# TC364_MainBoard_Power_V1_0.net
KiCad netlist of a schematic drawn in Altium Designer
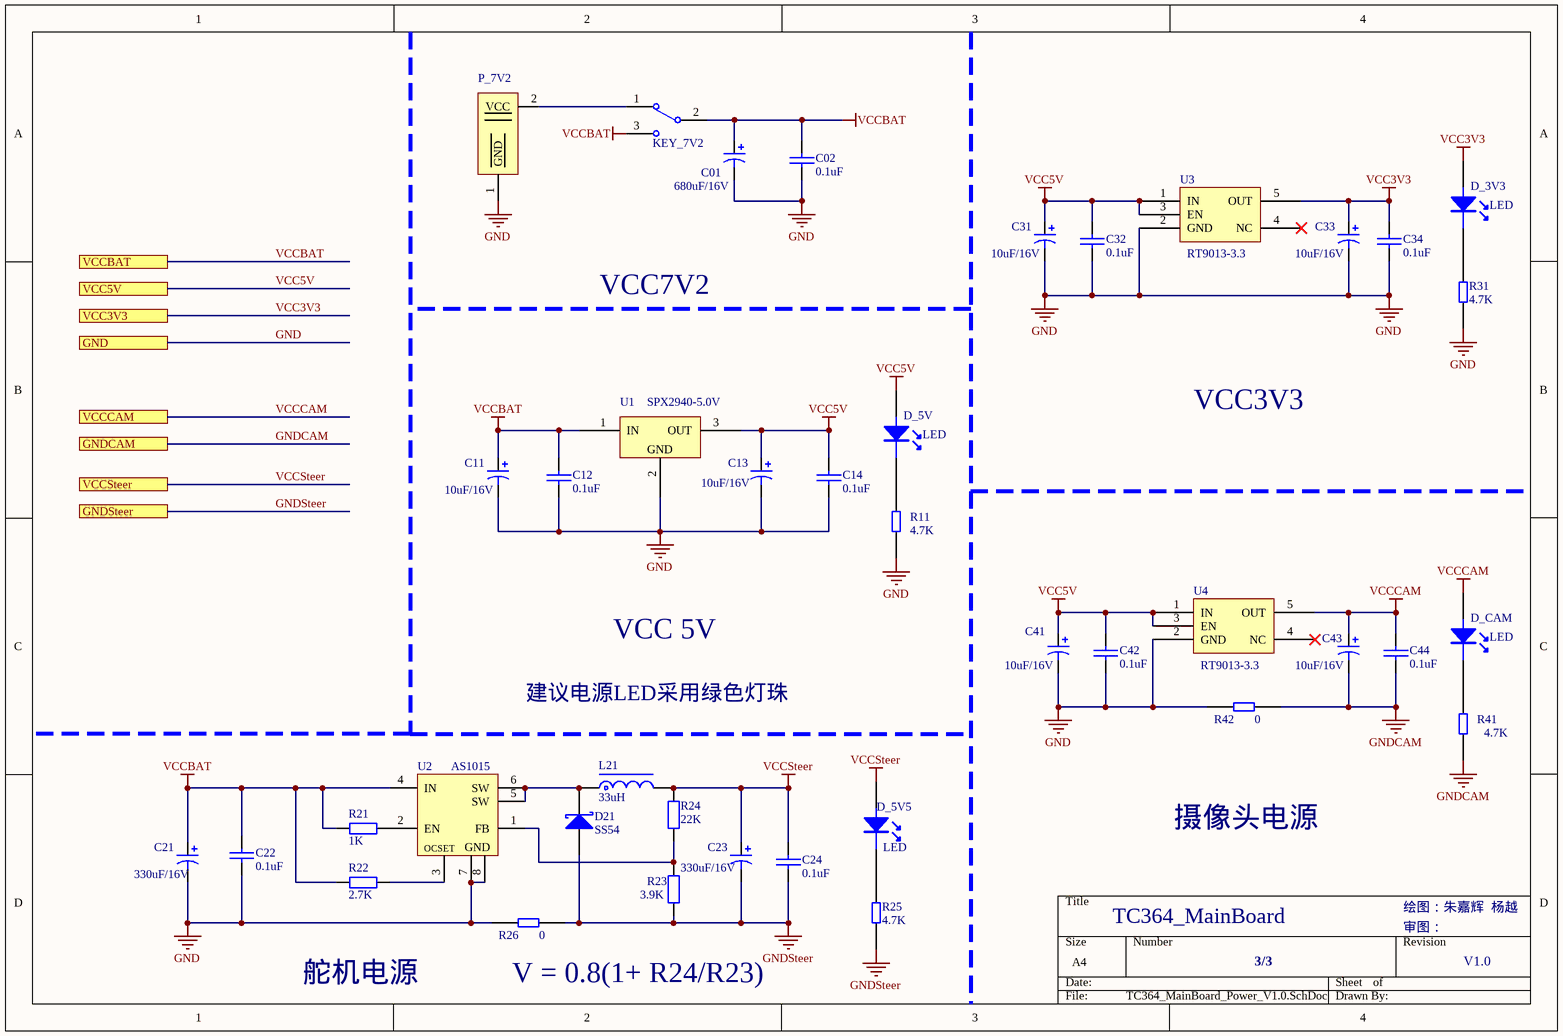
[diagram p0: TC364_MainBoard_Power_V1.0.SchDoc]

(export (version "E")
  (design (tool "Eeschema 10.0.6"))
  (components
    (comp (ref "C01")
      (value "680uF/16V")
      (footprint "CAP 3.5*8*11.5 - GD")
      (description "Polarized Capacitor (Radial)")
      (fields (field (name "PUBLISHER") "Altium Limited"))
      (libsource (lib "Miscellaneous Devices") (part "Cap Pol1"))
    )
    (comp (ref "C02")
      (value "0.1uF")
      (footprint "0805_C")
      (description "Capacitor")
      (libsource (lib "Protel99Lib_SCH") (part "CAP"))
    )
    (comp (ref "C11")
      (value "10uF/16V")
      (footprint "CASE-A_3216")
      (description "Polarized Capacitor (Radial)")
      (fields (field (name "PUBLISHER") "Altium Limited"))
      (libsource (lib "Miscellaneous Devices") (part "Cap Pol1"))
    )
    (comp (ref "C12")
      (value "0.1uF")
      (footprint "0805_C")
      (description "Capacitor")
      (libsource (lib "Protel99Lib_SCH") (part "CAP"))
    )
    (comp (ref "C13")
      (value "10uF/16V")
      (footprint "CASE-A_3216")
      (description "Polarized Capacitor (Radial)")
      (fields (field (name "PUBLISHER") "Altium Limited"))
      (libsource (lib "Miscellaneous Devices") (part "Cap Pol1"))
    )
    (comp (ref "C14")
      (value "0.1uF")
      (footprint "0805_C")
      (description "Capacitor")
      (libsource (lib "Protel99Lib_SCH") (part "CAP"))
    )
    (comp (ref "C21")
      (value "330uF/16V")
      (footprint "CAP 2.5*6.3*11.2 - BK")
      (description "Polarized Capacitor (Radial)")
      (fields (field (name "PUBLISHER") "Altium Limited"))
      (libsource (lib "Miscellaneous Devices") (part "Cap Pol1"))
    )
    (comp (ref "C22")
      (value "0.1uF")
      (footprint "0805_C")
      (description "Capacitor")
      (libsource (lib "Protel99Lib_SCH") (part "CAP"))
    )
    (comp (ref "C23")
      (value "330uF/16V")
      (footprint "CAP 2.5*6.3*11.2 - BK")
      (description "Polarized Capacitor (Radial)")
      (fields (field (name "PUBLISHER") "Altium Limited"))
      (libsource (lib "Miscellaneous Devices") (part "Cap Pol1"))
    )
    (comp (ref "C24")
      (value "0.1uF")
      (footprint "0805_C")
      (description "Capacitor")
      (libsource (lib "Protel99Lib_SCH") (part "CAP"))
    )
    (comp (ref "C31")
      (value "10uF/16V")
      (footprint "CASE-A_3216")
      (description "Polarized Capacitor (Radial)")
      (fields (field (name "PUBLISHER") "Altium Limited"))
      (libsource (lib "Miscellaneous Devices") (part "Cap Pol1"))
    )
    (comp (ref "C32")
      (value "0.1uF")
      (footprint "0805_C")
      (description "Capacitor")
      (libsource (lib "Protel99Lib_SCH") (part "CAP"))
    )
    (comp (ref "C33")
      (value "10uF/16V")
      (footprint "CASE-A_3216")
      (description "Polarized Capacitor (Radial)")
      (fields (field (name "PUBLISHER") "Altium Limited"))
      (libsource (lib "Miscellaneous Devices") (part "Cap Pol1"))
    )
    (comp (ref "C34")
      (value "0.1uF")
      (footprint "0805_C")
      (description "Capacitor")
      (libsource (lib "Protel99Lib_SCH") (part "CAP"))
    )
    (comp (ref "C41")
      (value "10uF/16V")
      (footprint "CASE-A_3216")
      (description "Polarized Capacitor (Radial)")
      (fields (field (name "PUBLISHER") "Altium Limited"))
      (libsource (lib "Miscellaneous Devices") (part "Cap Pol1"))
    )
    (comp (ref "C42")
      (value "0.1uF")
      (footprint "0805_C")
      (description "Capacitor")
      (libsource (lib "Protel99Lib_SCH") (part "CAP"))
    )
    (comp (ref "C43")
      (value "10uF/16V")
      (footprint "CASE-A_3216")
      (description "Polarized Capacitor (Radial)")
      (fields (field (name "PUBLISHER") "Altium Limited"))
      (libsource (lib "Miscellaneous Devices") (part "Cap Pol1"))
    )
    (comp (ref "C44")
      (value "0.1uF")
      (footprint "0805_C")
      (description "Capacitor")
      (libsource (lib "Protel99Lib_SCH") (part "CAP"))
    )
    (comp (ref "D21")
      (value "SS54")
      (footprint "SMA")
      (description "肖特基二极管")
      (libsource (lib "0.2 -  二极管-整流桥") (part "SS34"))
    )
    (comp (ref "D_3V3")
      (value "LED")
      (footprint "0805_LED_S1")
      (description "发光二极管")
      (libsource (lib "jianing") (part "LED"))
    )
    (comp (ref "D_5V")
      (value "LED")
      (footprint "0805_LED_S1")
      (description "发光二极管")
      (libsource (lib "jianing") (part "LED"))
    )
    (comp (ref "D_5V5")
      (value "LED")
      (footprint "0805_LED_S1")
      (description "发光二极管")
      (libsource (lib "jianing") (part "LED"))
    )
    (comp (ref "D_CAM")
      (value "LED")
      (footprint "0805_LED_S1")
      (description "发光二极管")
      (libsource (lib "jianing") (part "LED"))
    )
    (comp (ref "KEY_7V2")
      (value "SS-12F23")
      (footprint "KEY_7V2")
      (description "1路波动开关")
      (fields (field (name "版权归属") "封装库来自淘宝 ID：黄晶宝石"))
      (libsource (lib "0.7 - 常用按键-开关") (part "SSW-1P"))
    )
    (comp (ref "L21")
      (value "33uH")
      (footprint "7*7 L")
      (description "功率屏蔽电感")
      (fields (field (name "版权归属") "封装库来自淘宝 ID：黄晶宝石"))
      (libsource (lib "0.1 - 电阻-电容-电感") (part "L-CDRH"))
    )
    (comp (ref "P_7V2")
      (value "T_Type_Adapter")
      (footprint "T_Type_Adapter")
      (libsource (lib "Schlib1") (part "T_Type_Adapter"))
    )
    (comp (ref "R11") (value "4.7K") (footprint "0805_R") (libsource (lib "BaseLib_SCH") (part "RES")))
    (comp (ref "R21")
      (value "1K")
      (footprint "0603_R")
      (description "贴片电阻")
      (fields (field (name "版权归属") "源创客"))
      (libsource (lib "jianing") (part "RES"))
    )
    (comp (ref "R22")
      (value "2.7K")
      (footprint "0603_R")
      (description "贴片电阻")
      (fields (field (name "版权归属") "源创客"))
      (libsource (lib "jianing") (part "RES"))
    )
    (comp (ref "R23")
      (value "3.9K")
      (footprint "0603_R")
      (description "贴片电阻")
      (fields (field (name "版权归属") "源创客"))
      (libsource (lib "jianing") (part "RES"))
    )
    (comp (ref "R24")
      (value "22K")
      (footprint "0603_R")
      (description "贴片电阻")
      (fields (field (name "版权归属") "源创客"))
      (libsource (lib "jianing") (part "RES"))
    )
    (comp (ref "R25") (value "4.7K") (footprint "0805_R") (libsource (lib "BaseLib_SCH") (part "RES")))
    (comp (ref "R26") (value "0") (footprint "0805_R") (libsource (lib "BaseLib_SCH") (part "RES")))
    (comp (ref "R31") (value "4.7K") (footprint "0805_R") (libsource (lib "BaseLib_SCH") (part "RES")))
    (comp (ref "R41") (value "4.7K") (footprint "0805_R") (libsource (lib "BaseLib_SCH") (part "RES")))
    (comp (ref "R42") (value "0") (footprint "0805_R") (libsource (lib "BaseLib_SCH") (part "RES")))
    (comp (ref "U1")
      (value "SPX2940-5.0V")
      (footprint "TO-220(TO-220-3)")
      (description "5V稳压芯片")
      (fields (field (name "版权归属") "封装库来自淘宝 ID：黄晶宝石"))
      (libsource (lib "1.1 - 电源类芯片") (part "LM2940"))
    )
    (comp (ref "U2")
      (value "AS1015")
      (footprint "SOP-8_150mil")
      (description "可调升压芯片")
      (libsource (lib "1.0 - 常见芯片") (part "AS1015"))
    )
    (comp (ref "U3")
      (value "RT9013-3.3")
      (footprint "SOT-23-5")
      (libsource (lib "jianing") (part "RT9013-3.3"))
    )
    (comp (ref "U4")
      (value "RT9013-3.3")
      (footprint "SOT-23-5")
      (libsource (lib "jianing") (part "RT9013-3.3"))
    )
  )
  (nets
    (net (code "1") (name "GND") (class "Default")
      (node (ref "C01") (pin "2") (pinfunction "2_2") (pintype "passive"))
      (node (ref "C02") (pin "2") (pinfunction "2_2") (pintype "passive"))
      (node (ref "C11") (pin "2") (pinfunction "2_2") (pintype "passive"))
      (node (ref "C12") (pin "2") (pinfunction "2_2") (pintype "passive"))
      (node (ref "C13") (pin "2") (pinfunction "2_2") (pintype "passive"))
      (node (ref "C14") (pin "2") (pinfunction "2_2") (pintype "passive"))
      (node (ref "C21") (pin "2") (pinfunction "2_2") (pintype "passive"))
      (node (ref "C22") (pin "2") (pinfunction "2_2") (pintype "passive"))
      (node (ref "C31") (pin "2") (pinfunction "2_2") (pintype "passive"))
      (node (ref "C32") (pin "2") (pinfunction "2_2") (pintype "passive"))
      (node (ref "C33") (pin "2") (pinfunction "2_2") (pintype "passive"))
      (node (ref "C34") (pin "2") (pinfunction "2_2") (pintype "passive"))
      (node (ref "C41") (pin "2") (pinfunction "2_2") (pintype "passive"))
      (node (ref "C42") (pin "2") (pinfunction "2_2") (pintype "passive"))
      (node (ref "P_7V2") (pin "1") (pinfunction "GND_1") (pintype "passive"))
      (node (ref "R11") (pin "2") (pinfunction "2_2") (pintype "passive"))
      (node (ref "R26") (pin "2") (pinfunction "2_2") (pintype "passive"))
      (node (ref "R31") (pin "2") (pinfunction "2_2") (pintype "passive"))
      (node (ref "R42") (pin "2") (pinfunction "2_2") (pintype "passive"))
      (node (ref "U1") (pin "2") (pinfunction "GND_2") (pintype "power_in"))
      (node (ref "U2") (pin "7") (pinfunction "GND_7") (pintype "power_in"))
      (node (ref "U2") (pin "8") (pinfunction "GND_8") (pintype "power_in"))
      (node (ref "U3") (pin "2") (pinfunction "GND_2") (pintype "passive"))
      (node (ref "U4") (pin "2") (pinfunction "GND_2") (pintype "passive"))
    )
    (net (code "2") (name "GNDCAM") (class "Default")
      (node (ref "C43") (pin "2") (pinfunction "2_2") (pintype "passive"))
      (node (ref "C44") (pin "2") (pinfunction "2_2") (pintype "passive"))
      (node (ref "R41") (pin "2") (pinfunction "2_2") (pintype "passive"))
      (node (ref "R42") (pin "1") (pinfunction "1_1") (pintype "passive"))
    )
    (net (code "3") (name "GNDSteer") (class "Default")
      (node (ref "C23") (pin "2") (pinfunction "2_2") (pintype "passive"))
      (node (ref "C24") (pin "2") (pinfunction "2_2") (pintype "passive"))
      (node (ref "D21") (pin "1") (pinfunction "A_1") (pintype "passive"))
      (node (ref "R23") (pin "2") (pinfunction "2_2") (pintype "passive"))
      (node (ref "R25") (pin "2") (pinfunction "2_2") (pintype "passive"))
      (node (ref "R26") (pin "1") (pinfunction "1_1") (pintype "passive"))
    )
    (net (code "4") (name "Net-(D21-K)") (class "Default")
      (node (ref "D21") (pin "2") (pinfunction "K_2") (pintype "passive"))
      (node (ref "L21") (pin "1") (pinfunction "1_1") (pintype "passive"))
      (node (ref "U2") (pin "5") (pinfunction "SW_5") (pintype "power_in"))
      (node (ref "U2") (pin "6") (pinfunction "SW_6") (pintype "power_in"))
    )
    (net (code "5") (name "Net-(D_3V3-2)") (class "Default")
      (node (ref "D_3V3") (pin "K") (pinfunction "2_K") (pintype "passive"))
      (node (ref "R31") (pin "1") (pinfunction "1_1") (pintype "passive"))
    )
    (net (code "6") (name "Net-(D_5V-2)") (class "Default")
      (node (ref "D_5V") (pin "K") (pinfunction "2_K") (pintype "passive"))
      (node (ref "R11") (pin "1") (pinfunction "1_1") (pintype "passive"))
    )
    (net (code "7") (name "Net-(D_5V5-2)") (class "Default")
      (node (ref "D_5V5") (pin "K") (pinfunction "2_K") (pintype "passive"))
      (node (ref "R25") (pin "1") (pinfunction "1_1") (pintype "passive"))
    )
    (net (code "8") (name "Net-(D_CAM-2)") (class "Default")
      (node (ref "D_CAM") (pin "K") (pinfunction "2_K") (pintype "passive"))
      (node (ref "R41") (pin "1") (pinfunction "1_1") (pintype "passive"))
    )
    (net (code "9") (name "Net-(P_7V2-VCC)") (class "Default")
      (node (ref "KEY_7V2") (pin "1") (pinfunction "1_1") (pintype "passive"))
      (node (ref "P_7V2") (pin "2") (pinfunction "VCC_2") (pintype "passive"))
    )
    (net (code "10") (name "Net-(U2-EN)") (class "Default")
      (node (ref "R21") (pin "1") (pinfunction "1_1") (pintype "passive"))
      (node (ref "U2") (pin "2") (pinfunction "EN_2") (pintype "power_in"))
    )
    (net (code "11") (name "Net-(U2-FB)") (class "Default")
      (node (ref "R23") (pin "1") (pinfunction "1_1") (pintype "passive"))
      (node (ref "R24") (pin "2") (pinfunction "2_2") (pintype "passive"))
      (node (ref "U2") (pin "1") (pinfunction "FB_1") (pintype "power_in"))
    )
    (net (code "12") (name "Net-(U2-OCSET)") (class "Default")
      (node (ref "R22") (pin "1") (pinfunction "1_1") (pintype "passive"))
      (node (ref "U2") (pin "3") (pinfunction "OCSET_3") (pintype "power_in"))
    )
    (net (code "13") (name "VCC3V3") (class "Default")
      (node (ref "C33") (pin "1") (pinfunction "1_1") (pintype "passive"))
      (node (ref "C34") (pin "1") (pinfunction "1_1") (pintype "passive"))
      (node (ref "D_3V3") (pin "A") (pinfunction "1_A") (pintype "passive"))
      (node (ref "U3") (pin "5") (pinfunction "OUT_5") (pintype "passive"))
    )
    (net (code "14") (name "VCC5V") (class "Default")
      (node (ref "C13") (pin "1") (pinfunction "1_1") (pintype "passive"))
      (node (ref "C14") (pin "1") (pinfunction "1_1") (pintype "passive"))
      (node (ref "C31") (pin "1") (pinfunction "1_1") (pintype "passive"))
      (node (ref "C32") (pin "1") (pinfunction "1_1") (pintype "passive"))
      (node (ref "C41") (pin "1") (pinfunction "1_1") (pintype "passive"))
      (node (ref "C42") (pin "1") (pinfunction "1_1") (pintype "passive"))
      (node (ref "D_5V") (pin "A") (pinfunction "1_A") (pintype "passive"))
      (node (ref "U1") (pin "3") (pinfunction "OUT_3") (pintype "power_in"))
      (node (ref "U3") (pin "1") (pinfunction "IN_1") (pintype "passive"))
      (node (ref "U3") (pin "3") (pinfunction "EN_3") (pintype "passive"))
      (node (ref "U4") (pin "1") (pinfunction "IN_1") (pintype "passive"))
      (node (ref "U4") (pin "3") (pinfunction "EN_3") (pintype "passive"))
    )
    (net (code "15") (name "VCCBAT") (class "Default")
      (node (ref "C01") (pin "1") (pinfunction "1_1") (pintype "passive"))
      (node (ref "C02") (pin "1") (pinfunction "1_1") (pintype "passive"))
      (node (ref "C11") (pin "1") (pinfunction "1_1") (pintype "passive"))
      (node (ref "C12") (pin "1") (pinfunction "1_1") (pintype "passive"))
      (node (ref "C21") (pin "1") (pinfunction "1_1") (pintype "passive"))
      (node (ref "C22") (pin "1") (pinfunction "1_1") (pintype "passive"))
      (node (ref "KEY_7V2") (pin "2") (pinfunction "2_2") (pintype "passive"))
      (node (ref "KEY_7V2") (pin "3") (pinfunction "3_3") (pintype "passive"))
      (node (ref "R21") (pin "2") (pinfunction "2_2") (pintype "passive"))
      (node (ref "R22") (pin "2") (pinfunction "2_2") (pintype "passive"))
      (node (ref "U1") (pin "1") (pinfunction "IN_1") (pintype "power_in"))
      (node (ref "U2") (pin "4") (pinfunction "IN_4") (pintype "power_in"))
    )
    (net (code "16") (name "VCCCAM") (class "Default")
      (node (ref "C43") (pin "1") (pinfunction "1_1") (pintype "passive"))
      (node (ref "C44") (pin "1") (pinfunction "1_1") (pintype "passive"))
      (node (ref "D_CAM") (pin "A") (pinfunction "1_A") (pintype "passive"))
      (node (ref "U4") (pin "5") (pinfunction "OUT_5") (pintype "passive"))
    )
    (net (code "17") (name "VCCSteer") (class "Default")
      (node (ref "C23") (pin "1") (pinfunction "1_1") (pintype "passive"))
      (node (ref "C24") (pin "1") (pinfunction "1_1") (pintype "passive"))
      (node (ref "D_5V5") (pin "A") (pinfunction "1_A") (pintype "passive"))
      (node (ref "L21") (pin "2") (pinfunction "2_2") (pintype "passive"))
      (node (ref "R24") (pin "1") (pinfunction "1_1") (pintype "passive"))
    )
    (net (code "18") (name "unconnected-(U3-NC-Pad4)") (class "Default")
      (node (ref "U3") (pin "4") (pinfunction "NC_4") (pintype "passive+no_connect"))
    )
    (net (code "19") (name "unconnected-(U4-NC-Pad4)") (class "Default")
      (node (ref "U4") (pin "4") (pinfunction "NC_4") (pintype "passive+no_connect"))
    )
  )
)
